# onspeed.net
KiCad netlist of a schematic drawn in EAGLE
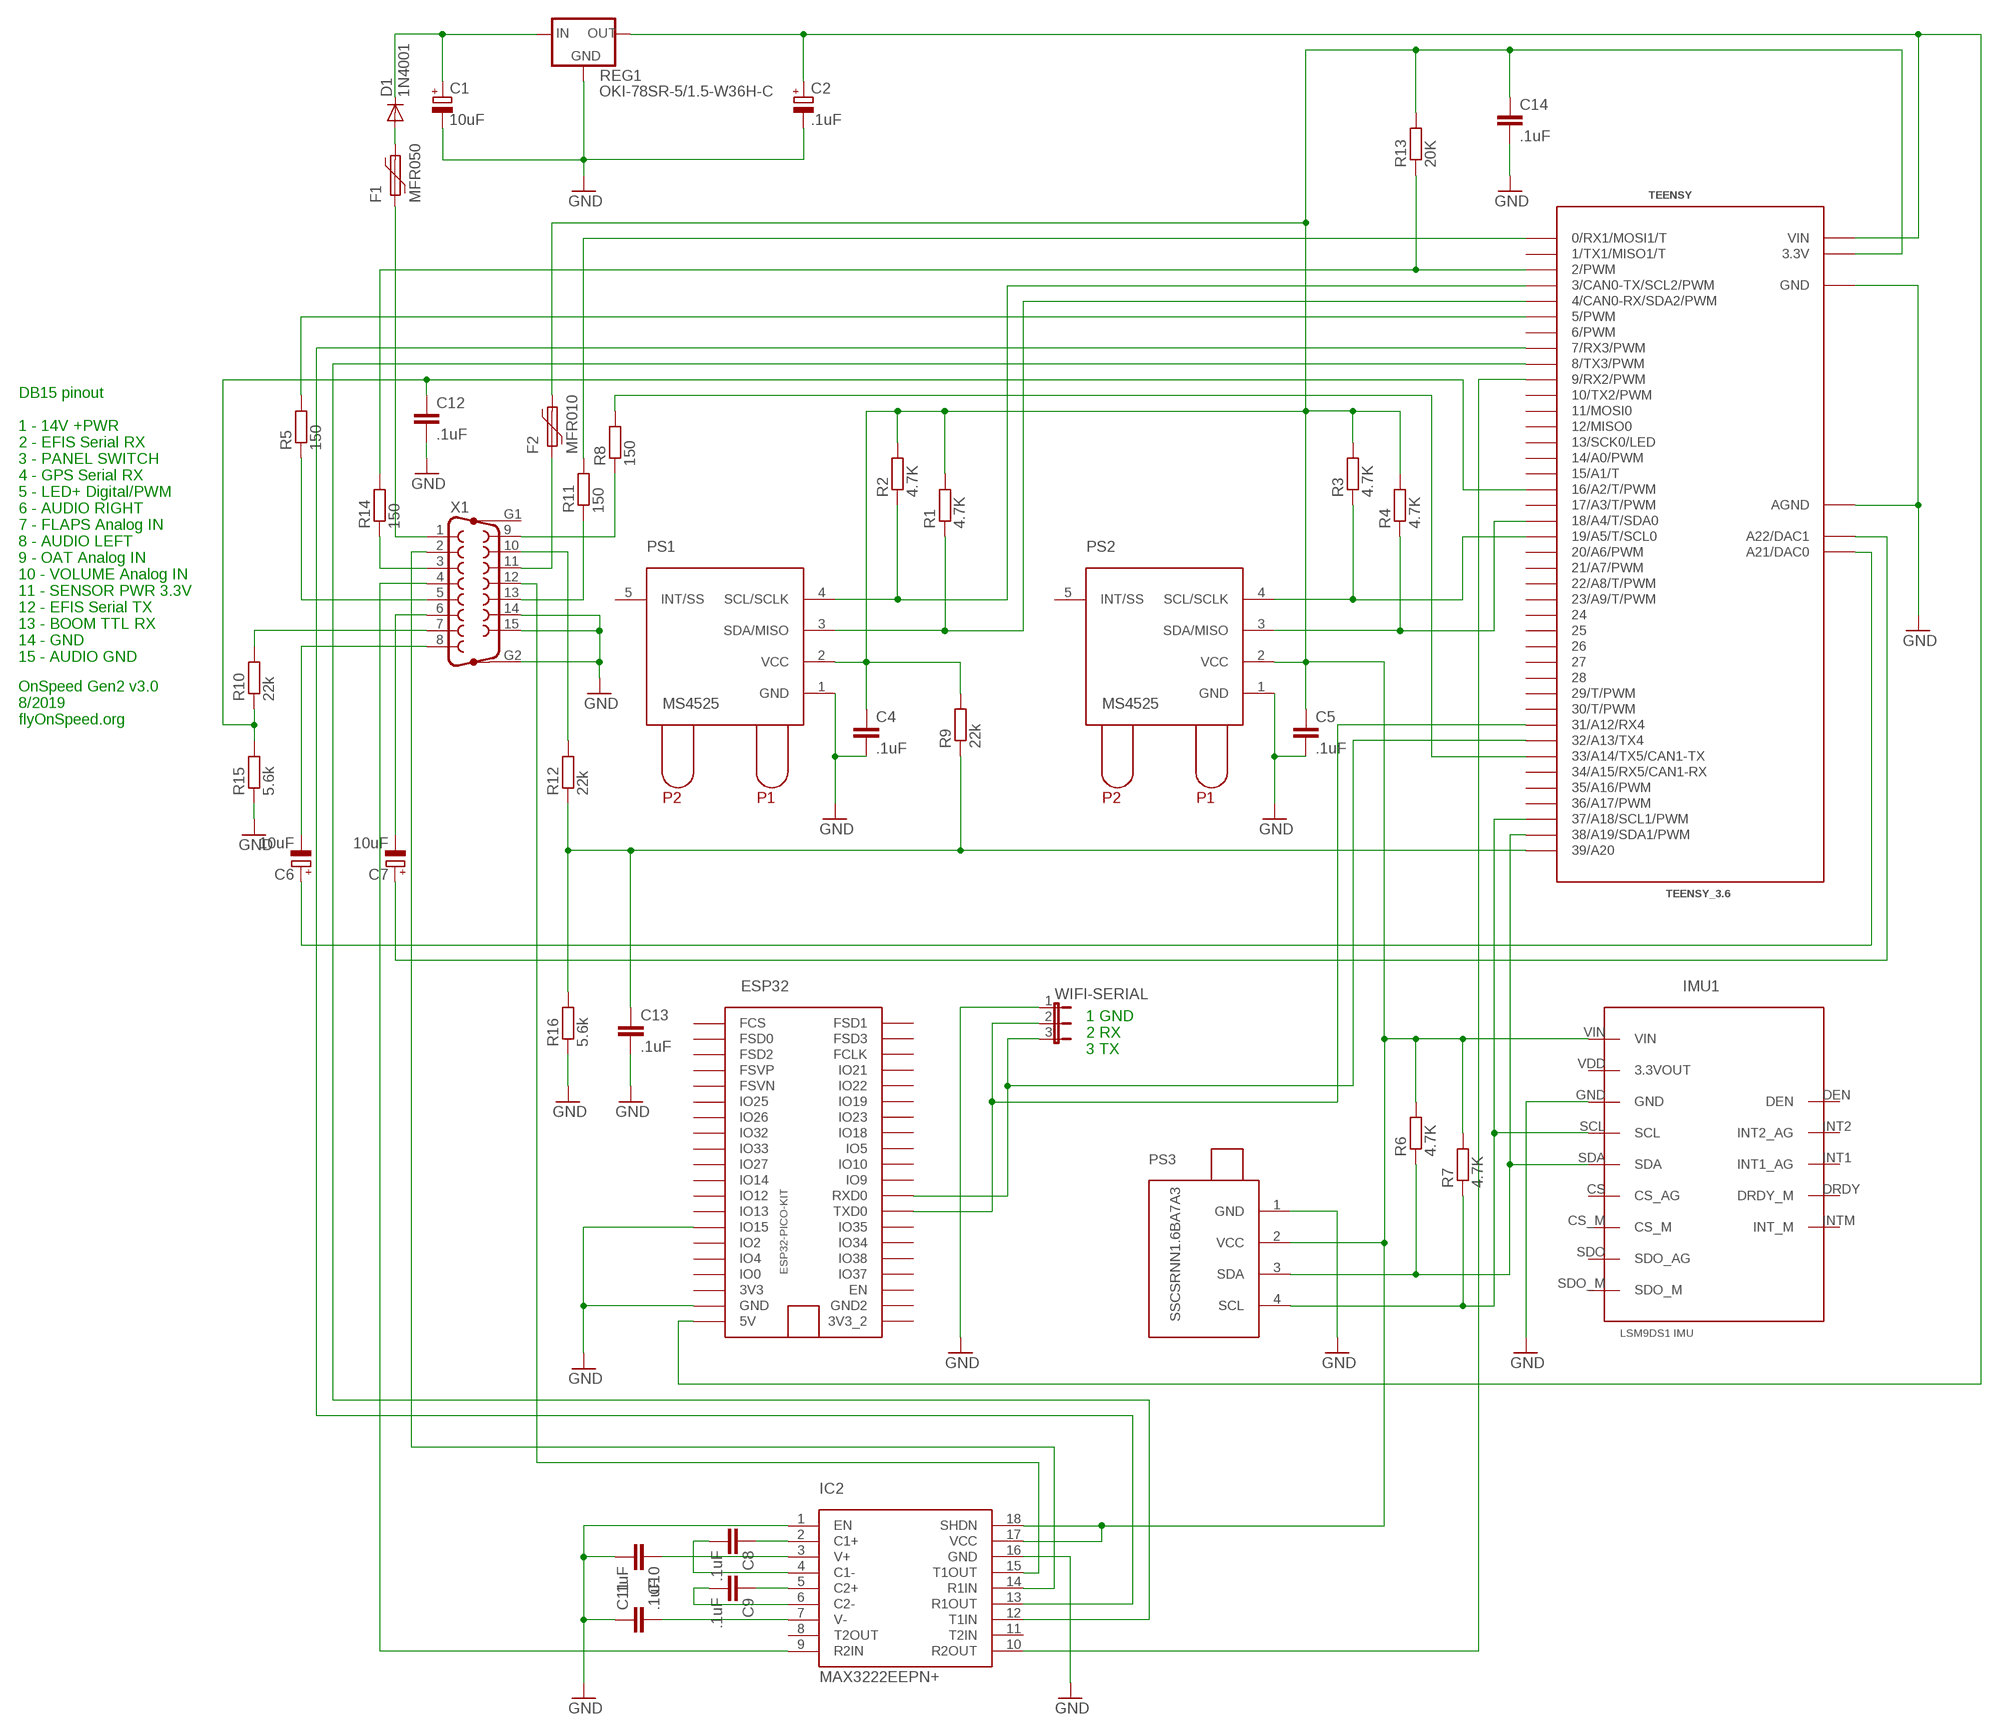
[diagram p0: schematic, sheet 1]

(export (version "E")
  (design (tool "Eeschema 10.0.6"))
  (components
    (comp (ref "C1")
      (value "10uF")
      (footprint "eagle-import:E2-5")
      (libsource (lib "eagle-import") (part "CPOL-EUE2-5"))
    )
    (comp (ref "C2")
      (value ".1uF")
      (footprint "eagle-import:E2-5")
      (libsource (lib "eagle-import") (part "CPOL-EUE2-5"))
    )
    (comp (ref "C4")
      (value ".1uF")
      (footprint "eagle-import:C025-025X050")
      (libsource (lib "eagle-import") (part "C-EU025-025X050"))
    )
    (comp (ref "C5")
      (value ".1uF")
      (footprint "eagle-import:C025-025X050")
      (libsource (lib "eagle-import") (part "C-EU025-025X050"))
    )
    (comp (ref "C6")
      (value "10uF")
      (footprint "eagle-import:E2-5")
      (libsource (lib "eagle-import") (part "CPOL-EUE2-5"))
    )
    (comp (ref "C7")
      (value "10uF")
      (footprint "eagle-import:E2-5")
      (libsource (lib "eagle-import") (part "CPOL-EUE2-5"))
    )
    (comp (ref "C8")
      (value ".1uF")
      (footprint "eagle-import:C025-025X050")
      (libsource (lib "eagle-import") (part "rcl_334_C-EU025-025X050"))
    )
    (comp (ref "C9")
      (value ".1uF")
      (footprint "eagle-import:C025-025X050")
      (libsource (lib "eagle-import") (part "rcl_334_C-EU025-025X050"))
    )
    (comp (ref "C10")
      (value ".1uF")
      (footprint "eagle-import:C025-025X050")
      (libsource (lib "eagle-import") (part "rcl_334_C-EU025-025X050"))
    )
    (comp (ref "C11")
      (value ".1uF")
      (footprint "eagle-import:C025-025X050")
      (libsource (lib "eagle-import") (part "rcl_334_C-EU025-025X050"))
    )
    (comp (ref "C12")
      (value ".1uF")
      (footprint "eagle-import:C025-025X050")
      (libsource (lib "eagle-import") (part "C-EU025-025X050"))
    )
    (comp (ref "C13")
      (value ".1uF")
      (footprint "eagle-import:C025-025X050")
      (libsource (lib "eagle-import") (part "C-EU025-025X050"))
    )
    (comp (ref "C14")
      (value ".1uF")
      (footprint "eagle-import:C025-025X050")
      (libsource (lib "eagle-import") (part "C-EU025-025X050"))
    )
    (comp (ref "D1")
      (value "1N4001")
      (footprint "eagle-import:DO41-10")
      (libsource (lib "eagle-import") (part "1N4001"))
    )
    (comp (ref "ESP32")
      (value "ESP32-PICO-KIT")
      (footprint "eagle-import:ESP32PICOKIT")
      (libsource (lib "eagle-import") (part "ESP32-PICO-KITPICO"))
    )
    (comp (ref "F1")
      (value "MFR050")
      (footprint "eagle-import:MF-5,1B")
      (libsource (lib "eagle-import") (part "MF-R055-5,1B"))
    )
    (comp (ref "F2")
      (value "MFR010")
      (footprint "eagle-import:MF-5,1B")
      (libsource (lib "eagle-import") (part "MF-R055-5,1B"))
    )
    (comp (ref "IC2")
      (value "MAX3222EEPN+")
      (footprint "eagle-import:DIL18")
      (libsource (lib "eagle-import") (part "MAX3222EEPN+"))
    )
    (comp (ref "IMU1")
      (value "LSM9DS1 IMU")
      (footprint "eagle-import:LSM9DS1_BREAKOUT")
      (libsource (lib "eagle-import") (part "LSM9DS1_BREAKOUT"))
    )
    (comp (ref "PS1")
      (value "MS4525")
      (footprint "eagle-import:DIL08-500")
      (libsource (lib "eagle-import") (part "MS4525"))
    )
    (comp (ref "PS2")
      (value "MS4525")
      (footprint "eagle-import:DIL08-500")
      (libsource (lib "eagle-import") (part "MS4525"))
    )
    (comp (ref "PS3")
      (value "SSCSRNN1.6BA7A3")
      (footprint "eagle-import:SIP-RN")
      (libsource (lib "eagle-import") (part "SSCSRNN1.6BA7A3"))
    )
    (comp (ref "R1")
      (value "4.7K")
      (footprint "eagle-import:0207_10")
      (libsource (lib "eagle-import") (part "R-EU_0207/10"))
    )
    (comp (ref "R2")
      (value "4.7K")
      (footprint "eagle-import:0207_10")
      (libsource (lib "eagle-import") (part "R-EU_0207/10"))
    )
    (comp (ref "R3")
      (value "4.7K")
      (footprint "eagle-import:0207_10")
      (libsource (lib "eagle-import") (part "R-EU_0207/10"))
    )
    (comp (ref "R4")
      (value "4.7K")
      (footprint "eagle-import:0207_10")
      (libsource (lib "eagle-import") (part "R-EU_0207/10"))
    )
    (comp (ref "R5")
      (value "150")
      (footprint "eagle-import:0207_10")
      (libsource (lib "eagle-import") (part "R-EU_0207/10"))
    )
    (comp (ref "R6")
      (value "4.7K")
      (footprint "eagle-import:0207_10")
      (libsource (lib "eagle-import") (part "R-EU_0207/10"))
    )
    (comp (ref "R7")
      (value "4.7K")
      (footprint "eagle-import:0207_10")
      (libsource (lib "eagle-import") (part "R-EU_0207/10"))
    )
    (comp (ref "R8")
      (value "150")
      (footprint "eagle-import:0207_10")
      (libsource (lib "eagle-import") (part "R-EU_0207/10"))
    )
    (comp (ref "R9")
      (value "22k")
      (footprint "eagle-import:0207_10")
      (libsource (lib "eagle-import") (part "R-EU_0207/10"))
    )
    (comp (ref "R10")
      (value "22k")
      (footprint "eagle-import:0207_10")
      (libsource (lib "eagle-import") (part "R-EU_0207/10"))
    )
    (comp (ref "R11")
      (value "150")
      (footprint "eagle-import:0207_10")
      (libsource (lib "eagle-import") (part "R-EU_0207/10"))
    )
    (comp (ref "R12")
      (value "22k")
      (footprint "eagle-import:0207_10")
      (libsource (lib "eagle-import") (part "R-EU_0207/10"))
    )
    (comp (ref "R13")
      (value "20K")
      (footprint "eagle-import:0207_10")
      (libsource (lib "eagle-import") (part "R-EU_0207/10"))
    )
    (comp (ref "R14")
      (value "150")
      (footprint "eagle-import:0207_10")
      (libsource (lib "eagle-import") (part "R-EU_0207/10"))
    )
    (comp (ref "R15")
      (value "5.6k")
      (footprint "eagle-import:0207_10")
      (libsource (lib "eagle-import") (part "R-EU_0207/10"))
    )
    (comp (ref "R16")
      (value "5.6k")
      (footprint "eagle-import:0207_10")
      (libsource (lib "eagle-import") (part "R-EU_0207/10"))
    )
    (comp (ref "REG1")
      (value "OKI-78SR-5/1.5-W36H-C")
      (footprint "eagle-import:SIP3H")
      (libsource (lib "eagle-import") (part "OKI-78SR-5/1.5-W36H-C"))
    )
    (comp (ref "TEENSY")
      (value "TEENSY_3.6")
      (footprint "eagle-import:TEENSY_3.6_DIL")
      (libsource (lib "eagle-import") (part "TEENSY_3.6_DIL"))
    )
    (comp (ref "WIFI-SERIAL")
      (value "JP2E")
      (footprint "eagle-import:JP2")
      (libsource (lib "eagle-import") (part "JP2E"))
    )
    (comp (ref "X1")
      (value "F15HP")
      (footprint "eagle-import:F15HP")
      (libsource (lib "eagle-import") (part "F15HP"))
    )
  )
  (nets
    (net (code "1") (name "GND") (class "Default")
      (node (ref "C1") (pin "-") (pinfunction "-_-") (pintype "passive"))
      (node (ref "C10") (pin "2") (pinfunction "2_2") (pintype "passive"))
      (node (ref "C11") (pin "1") (pinfunction "1_1") (pintype "passive"))
      (node (ref "C12") (pin "2") (pinfunction "2_2") (pintype "passive"))
      (node (ref "C13") (pin "2") (pinfunction "2_2") (pintype "passive"))
      (node (ref "C14") (pin "2") (pinfunction "2_2") (pintype "passive"))
      (node (ref "C2") (pin "-") (pinfunction "-_-") (pintype "passive"))
      (node (ref "C4") (pin "2") (pinfunction "2_2") (pintype "passive"))
      (node (ref "C5") (pin "2") (pinfunction "2_2") (pintype "passive"))
      (node (ref "ESP32") (pin "P$GND") (pinfunction "GND_P$GND") (pintype "bidirectional"))
      (node (ref "ESP32") (pin "P$IO15") (pinfunction "IO15_P$IO15") (pintype "bidirectional"))
      (node (ref "IC2") (pin "1") (pinfunction "EN_1") (pintype "bidirectional"))
      (node (ref "IC2") (pin "16") (pinfunction "GND_16") (pintype "bidirectional"))
      (node (ref "IMU1") (pin "GND") (pinfunction "GND_GND") (pintype "power_in"))
      (node (ref "PS1") (pin "1") (pinfunction "GND_1") (pintype "power_in"))
      (node (ref "PS2") (pin "1") (pinfunction "GND_1") (pintype "power_in"))
      (node (ref "PS3") (pin "1") (pinfunction "GND_1") (pintype "bidirectional"))
      (node (ref "R15") (pin "1") (pinfunction "1_1") (pintype "passive"))
      (node (ref "R16") (pin "1") (pinfunction "1_1") (pintype "passive"))
      (node (ref "REG1") (pin "2") (pinfunction "GND_2") (pintype "input"))
      (node (ref "TEENSY") (pin "AGND") (pinfunction "AGND_AGND") (pintype "power_in"))
      (node (ref "TEENSY") (pin "GND") (pinfunction "GND_GND") (pintype "power_in"))
      (node (ref "TEENSY") (pin "GND1") (pinfunction "GND_GND1") (pintype "power_in"))
      (node (ref "WIFI-SERIAL") (pin "1") (pinfunction "1_1") (pintype "passive"))
      (node (ref "X1") (pin "14") (pinfunction "14_14") (pintype "passive"))
      (node (ref "X1") (pin "15") (pinfunction "15_15") (pintype "passive"))
      (node (ref "X1") (pin "G2") (pinfunction "G2_G2") (pintype "passive"))
    )
    (net (code "2") (name "Net-(C6-Pad-)") (class "Default")
      (node (ref "C6") (pin "-") (pinfunction "-_-") (pintype "passive"))
      (node (ref "X1") (pin "8") (pinfunction "8_8") (pintype "passive"))
    )
    (net (code "3") (name "Net-(C7-Pad-)") (class "Default")
      (node (ref "C7") (pin "-") (pinfunction "-_-") (pintype "passive"))
      (node (ref "X1") (pin "6") (pinfunction "6_6") (pintype "passive"))
    )
    (net (code "4") (name "Net-(C13-Pad1)") (class "Default")
      (node (ref "C13") (pin "1") (pinfunction "1_1") (pintype "passive"))
      (node (ref "R12") (pin "1") (pinfunction "1_1") (pintype "passive"))
      (node (ref "R16") (pin "2") (pinfunction "2_2") (pintype "passive"))
      (node (ref "R9") (pin "1") (pinfunction "1_1") (pintype "passive"))
      (node (ref "TEENSY") (pin "39/A20") (pinfunction "39/A20_39/A20") (pintype "bidirectional"))
    )
    (net (code "5") (name "Net-(D1-PadA)") (class "Default")
      (node (ref "D1") (pin "A") (pinfunction "A_A") (pintype "passive"))
      (node (ref "F1") (pin "2") (pinfunction "2_2") (pintype "passive"))
    )
    (net (code "6") (name "Net-(ESP32-5V)") (class "Default")
      (node (ref "C2") (pin "+") (pinfunction "+_+") (pintype "passive"))
      (node (ref "ESP32") (pin "P$5V") (pinfunction "5V_P$5V") (pintype "bidirectional"))
      (node (ref "REG1") (pin "3") (pinfunction "OUT_3") (pintype "passive"))
      (node (ref "TEENSY") (pin "VIN") (pinfunction "VIN_VIN") (pintype "power_in"))
    )
    (net (code "7") (name "Net-(ESP32-RXD0)") (class "Default")
      (node (ref "ESP32") (pin "P$RXD0") (pinfunction "RXD0_P$RXD0") (pintype "bidirectional"))
      (node (ref "TEENSY") (pin "32/A13") (pinfunction "32/A13/TX4_32/A13") (pintype "bidirectional"))
      (node (ref "WIFI-SERIAL") (pin "3") (pinfunction "3_3") (pintype "passive"))
    )
    (net (code "8") (name "Net-(ESP32-TXD0)") (class "Default")
      (node (ref "ESP32") (pin "P$TXD0") (pinfunction "TXD0_P$TXD0") (pintype "bidirectional"))
      (node (ref "TEENSY") (pin "31/A12") (pinfunction "31/A12/RX4_31/A12") (pintype "bidirectional"))
      (node (ref "WIFI-SERIAL") (pin "2") (pinfunction "2_2") (pintype "passive"))
    )
    (net (code "9") (name "Net-(F1-Pad1)") (class "Default")
      (node (ref "F1") (pin "1") (pinfunction "1_1") (pintype "passive"))
      (node (ref "X1") (pin "1") (pinfunction "1_1") (pintype "passive"))
    )
    (net (code "10") (name "Net-(F2-Pad1)") (class "Default")
      (node (ref "F2") (pin "1") (pinfunction "1_1") (pintype "passive"))
      (node (ref "X1") (pin "11") (pinfunction "11_11") (pintype "passive"))
    )
    (net (code "11") (name "Net-(IC2-C1+)") (class "Default")
      (node (ref "C8") (pin "1") (pinfunction "1_1") (pintype "passive"))
      (node (ref "IC2") (pin "2") (pinfunction "C1+_2") (pintype "bidirectional"))
    )
    (net (code "12") (name "Net-(IC2-C1-)") (class "Default")
      (node (ref "C8") (pin "2") (pinfunction "2_2") (pintype "passive"))
      (node (ref "IC2") (pin "4") (pinfunction "C1-_4") (pintype "bidirectional"))
    )
    (net (code "13") (name "Net-(IC2-C2+)") (class "Default")
      (node (ref "C9") (pin "1") (pinfunction "1_1") (pintype "passive"))
      (node (ref "IC2") (pin "5") (pinfunction "C2+_5") (pintype "bidirectional"))
    )
    (net (code "14") (name "Net-(IC2-C2-)") (class "Default")
      (node (ref "C9") (pin "2") (pinfunction "2_2") (pintype "passive"))
      (node (ref "IC2") (pin "6") (pinfunction "C2-_6") (pintype "bidirectional"))
    )
    (net (code "15") (name "Net-(IC2-R1IN)") (class "Default")
      (node (ref "IC2") (pin "14") (pinfunction "R1IN_14") (pintype "bidirectional"))
      (node (ref "X1") (pin "2") (pinfunction "2_2") (pintype "passive"))
    )
    (net (code "16") (name "Net-(IC2-R1OUT)") (class "Default")
      (node (ref "IC2") (pin "13") (pinfunction "R1OUT_13") (pintype "bidirectional"))
      (node (ref "TEENSY") (pin "7") (pinfunction "7/RX3/PWM_7") (pintype "bidirectional"))
    )
    (net (code "17") (name "Net-(IC2-R2IN)") (class "Default")
      (node (ref "IC2") (pin "9") (pinfunction "R2IN_9") (pintype "bidirectional"))
      (node (ref "X1") (pin "4") (pinfunction "4_4") (pintype "passive"))
    )
    (net (code "18") (name "Net-(IC2-R2OUT)") (class "Default")
      (node (ref "IC2") (pin "10") (pinfunction "R2OUT_10") (pintype "bidirectional"))
      (node (ref "TEENSY") (pin "9") (pinfunction "9/RX2/PWM_9") (pintype "bidirectional"))
    )
    (net (code "19") (name "Net-(IC2-SHDN)") (class "Default")
      (node (ref "C14") (pin "1") (pinfunction "1_1") (pintype "passive"))
      (node (ref "C4") (pin "1") (pinfunction "1_1") (pintype "passive"))
      (node (ref "C5") (pin "1") (pinfunction "1_1") (pintype "passive"))
      (node (ref "F2") (pin "2") (pinfunction "2_2") (pintype "passive"))
      (node (ref "IC2") (pin "17") (pinfunction "VCC_17") (pintype "bidirectional"))
      (node (ref "IC2") (pin "18") (pinfunction "SHDN_18") (pintype "bidirectional"))
      (node (ref "IMU1") (pin "VIN") (pinfunction "VIN_VIN") (pintype "power_in"))
      (node (ref "PS1") (pin "2") (pinfunction "VCC_2") (pintype "power_in"))
      (node (ref "PS2") (pin "2") (pinfunction "VCC_2") (pintype "power_in"))
      (node (ref "PS3") (pin "2") (pinfunction "VCC_2") (pintype "bidirectional"))
      (node (ref "R1") (pin "2") (pinfunction "2_2") (pintype "passive"))
      (node (ref "R13") (pin "2") (pinfunction "2_2") (pintype "passive"))
      (node (ref "R2") (pin "2") (pinfunction "2_2") (pintype "passive"))
      (node (ref "R3") (pin "2") (pinfunction "2_2") (pintype "passive"))
      (node (ref "R4") (pin "2") (pinfunction "2_2") (pintype "passive"))
      (node (ref "R6") (pin "2") (pinfunction "2_2") (pintype "passive"))
      (node (ref "R7") (pin "2") (pinfunction "2_2") (pintype "passive"))
      (node (ref "R9") (pin "2") (pinfunction "2_2") (pintype "passive"))
      (node (ref "TEENSY") (pin "3.3V") (pinfunction "3.3V_3.3V") (pintype "power_in"))
      (node (ref "TEENSY") (pin "3.3V3") (pinfunction "3.3V_3.3V3") (pintype "power_in"))
    )
    (net (code "20") (name "Net-(IC2-T1IN)") (class "Default")
      (node (ref "IC2") (pin "12") (pinfunction "T1IN_12") (pintype "bidirectional"))
      (node (ref "TEENSY") (pin "8") (pinfunction "8/TX3/PWM_8") (pintype "bidirectional"))
    )
    (net (code "21") (name "Net-(IC2-T1OUT)") (class "Default")
      (node (ref "IC2") (pin "15") (pinfunction "T1OUT_15") (pintype "bidirectional"))
      (node (ref "X1") (pin "12") (pinfunction "12_12") (pintype "passive"))
    )
    (net (code "22") (name "Net-(IC2-V+)") (class "Default")
      (node (ref "C10") (pin "1") (pinfunction "1_1") (pintype "passive"))
      (node (ref "IC2") (pin "3") (pinfunction "V+_3") (pintype "bidirectional"))
    )
    (net (code "23") (name "Net-(IC2-V-)") (class "Default")
      (node (ref "C11") (pin "2") (pinfunction "2_2") (pintype "passive"))
      (node (ref "IC2") (pin "7") (pinfunction "V-_7") (pintype "bidirectional"))
    )
    (net (code "24") (name "Net-(PS1-SCL{slash}SCLK)") (class "Default")
      (node (ref "PS1") (pin "4") (pinfunction "SCL/SCLK_4") (pintype "bidirectional"))
      (node (ref "R2") (pin "1") (pinfunction "1_1") (pintype "passive"))
      (node (ref "TEENSY") (pin "3") (pinfunction "3/CAN0-TX/SCL2/PWM_3") (pintype "bidirectional"))
    )
    (net (code "25") (name "Net-(PS1-SDA{slash}MISO)") (class "Default")
      (node (ref "PS1") (pin "3") (pinfunction "SDA/MISO_3") (pintype "bidirectional"))
      (node (ref "R1") (pin "1") (pinfunction "1_1") (pintype "passive"))
      (node (ref "TEENSY") (pin "4") (pinfunction "4/CAN0-RX/SDA2/PWM_4") (pintype "bidirectional"))
    )
    (net (code "26") (name "Net-(PS2-SCL{slash}SCLK)") (class "Default")
      (node (ref "PS2") (pin "4") (pinfunction "SCL/SCLK_4") (pintype "bidirectional"))
      (node (ref "R3") (pin "1") (pinfunction "1_1") (pintype "passive"))
      (node (ref "TEENSY") (pin "19/A5") (pinfunction "19/A5/T/SCL0_19/A5") (pintype "bidirectional"))
    )
    (net (code "27") (name "Net-(PS2-SDA{slash}MISO)") (class "Default")
      (node (ref "PS2") (pin "3") (pinfunction "SDA/MISO_3") (pintype "bidirectional"))
      (node (ref "R4") (pin "1") (pinfunction "1_1") (pintype "passive"))
      (node (ref "TEENSY") (pin "18/A4") (pinfunction "18/A4/T/SDA0_18/A4") (pintype "bidirectional"))
    )
    (net (code "28") (name "Net-(PS3-SCL)") (class "Default")
      (node (ref "IMU1") (pin "SCL") (pinfunction "SCL_SCL") (pintype "bidirectional"))
      (node (ref "PS3") (pin "4") (pinfunction "SCL_4") (pintype "bidirectional"))
      (node (ref "R7") (pin "1") (pinfunction "1_1") (pintype "passive"))
      (node (ref "TEENSY") (pin "37/A18") (pinfunction "37/A18/SCL1/PWM_37/A18") (pintype "bidirectional"))
    )
    (net (code "29") (name "Net-(PS3-SDA)") (class "Default")
      (node (ref "IMU1") (pin "SDA") (pinfunction "SDA_SDA") (pintype "bidirectional"))
      (node (ref "PS3") (pin "3") (pinfunction "SDA_3") (pintype "bidirectional"))
      (node (ref "R6") (pin "1") (pinfunction "1_1") (pintype "passive"))
      (node (ref "TEENSY") (pin "38/A19") (pinfunction "38/A19/SDA1/PWM_38/A19") (pintype "bidirectional"))
    )
    (net (code "30") (name "Net-(R5-Pad1)") (class "Default")
      (node (ref "R5") (pin "1") (pinfunction "1_1") (pintype "passive"))
      (node (ref "X1") (pin "5") (pinfunction "5_5") (pintype "passive"))
    )
    (net (code "31") (name "Net-(R8-Pad1)") (class "Default")
      (node (ref "R8") (pin "1") (pinfunction "1_1") (pintype "passive"))
      (node (ref "X1") (pin "9") (pinfunction "9_9") (pintype "passive"))
    )
    (net (code "32") (name "Net-(R10-Pad2)") (class "Default")
      (node (ref "R10") (pin "2") (pinfunction "2_2") (pintype "passive"))
      (node (ref "X1") (pin "7") (pinfunction "7_7") (pintype "passive"))
    )
    (net (code "33") (name "Net-(R11-Pad1)") (class "Default")
      (node (ref "R11") (pin "1") (pinfunction "1_1") (pintype "passive"))
      (node (ref "X1") (pin "13") (pinfunction "13_13") (pintype "passive"))
    )
    (net (code "34") (name "Net-(R12-Pad2)") (class "Default")
      (node (ref "R12") (pin "2") (pinfunction "2_2") (pintype "passive"))
      (node (ref "X1") (pin "10") (pinfunction "10_10") (pintype "passive"))
    )
    (net (code "35") (name "Net-(R14-Pad1)") (class "Default")
      (node (ref "R14") (pin "1") (pinfunction "1_1") (pintype "passive"))
      (node (ref "X1") (pin "3") (pinfunction "3_3") (pintype "passive"))
    )
    (net (code "36") (name "Net-(REG1-IN)") (class "Default")
      (node (ref "C1") (pin "+") (pinfunction "+_+") (pintype "passive"))
      (node (ref "D1") (pin "C") (pinfunction "C_C") (pintype "passive"))
      (node (ref "REG1") (pin "1") (pinfunction "IN_1") (pintype "input"))
    )
    (net (code "37") (name "Net-(TEENSY-0{slash}RX1{slash}MOSI1{slash}T)") (class "Default")
      (node (ref "R11") (pin "2") (pinfunction "2_2") (pintype "passive"))
      (node (ref "TEENSY") (pin "0") (pinfunction "0/RX1/MOSI1/T_0") (pintype "bidirectional"))
    )
    (net (code "38") (name "Net-(TEENSY-2{slash}PWM)") (class "Default")
      (node (ref "R13") (pin "1") (pinfunction "1_1") (pintype "passive"))
      (node (ref "R14") (pin "2") (pinfunction "2_2") (pintype "passive"))
      (node (ref "TEENSY") (pin "2") (pinfunction "2/PWM_2") (pintype "bidirectional"))
    )
    (net (code "39") (name "Net-(TEENSY-5{slash}PWM)") (class "Default")
      (node (ref "R5") (pin "2") (pinfunction "2_2") (pintype "passive"))
      (node (ref "TEENSY") (pin "5") (pinfunction "5/PWM_5") (pintype "bidirectional"))
    )
    (net (code "40") (name "Net-(TEENSY-16{slash}A2{slash}T{slash}PWM)") (class "Default")
      (node (ref "C12") (pin "1") (pinfunction "1_1") (pintype "passive"))
      (node (ref "R10") (pin "1") (pinfunction "1_1") (pintype "passive"))
      (node (ref "R15") (pin "2") (pinfunction "2_2") (pintype "passive"))
      (node (ref "TEENSY") (pin "16/A2") (pinfunction "16/A2/T/PWM_16/A2") (pintype "bidirectional"))
    )
    (net (code "41") (name "Net-(TEENSY-33{slash}A14{slash}TX5{slash}CAN1-TX)") (class "Default")
      (node (ref "R8") (pin "2") (pinfunction "2_2") (pintype "passive"))
      (node (ref "TEENSY") (pin "33/A14") (pinfunction "33/A14/TX5/CAN1-TX_33/A14") (pintype "bidirectional"))
    )
    (net (code "42") (name "Net-(TEENSY-A21{slash}DAC0)") (class "Default")
      (node (ref "C6") (pin "+") (pinfunction "+_+") (pintype "passive"))
      (node (ref "TEENSY") (pin "A21") (pinfunction "A21/DAC0_A21") (pintype "bidirectional"))
    )
    (net (code "43") (name "Net-(TEENSY-A22{slash}DAC1)") (class "Default")
      (node (ref "C7") (pin "+") (pinfunction "+_+") (pintype "passive"))
      (node (ref "TEENSY") (pin "A22") (pinfunction "A22/DAC1_A22") (pintype "bidirectional"))
    )
    (net (code "44") (name "unconnected-(ESP32-3V3-PadP$3V3)") (class "Default")
      (node (ref "ESP32") (pin "P$3V3") (pinfunction "3V3_P$3V3") (pintype "bidirectional"))
    )
    (net (code "45") (name "unconnected-(ESP32-3V3_2-PadP$3V3_2)") (class "Default")
      (node (ref "ESP32") (pin "P$3V3_2") (pinfunction "3V3_2_P$3V3_2") (pintype "bidirectional"))
    )
    (net (code "46") (name "unconnected-(ESP32-EN-PadP$EN)") (class "Default")
      (node (ref "ESP32") (pin "P$EN") (pinfunction "EN_P$EN") (pintype "bidirectional"))
    )
    (net (code "47") (name "unconnected-(ESP32-FCLK-PadP$FCLK)") (class "Default")
      (node (ref "ESP32") (pin "P$FCLK") (pinfunction "FCLK_P$FCLK") (pintype "bidirectional"))
    )
    (net (code "48") (name "unconnected-(ESP32-FCS-PadP$FCS)") (class "Default")
      (node (ref "ESP32") (pin "P$FCS") (pinfunction "FCS_P$FCS") (pintype "bidirectional"))
    )
    (net (code "49") (name "unconnected-(ESP32-FSD0-PadP$FSD0)") (class "Default")
      (node (ref "ESP32") (pin "P$FSD0") (pinfunction "FSD0_P$FSD0") (pintype "bidirectional"))
    )
    (net (code "50") (name "unconnected-(ESP32-FSD1-PadP$FSD1)") (class "Default")
      (node (ref "ESP32") (pin "P$FSD1") (pinfunction "FSD1_P$FSD1") (pintype "bidirectional"))
    )
    (net (code "51") (name "unconnected-(ESP32-FSD2-PadP$FSD2)") (class "Default")
      (node (ref "ESP32") (pin "P$FSD2") (pinfunction "FSD2_P$FSD2") (pintype "bidirectional"))
    )
    (net (code "52") (name "unconnected-(ESP32-FSD3-PadP$FSD3)") (class "Default")
      (node (ref "ESP32") (pin "P$FSD3") (pinfunction "FSD3_P$FSD3") (pintype "bidirectional"))
    )
    (net (code "53") (name "unconnected-(ESP32-FSVN-PadP$FSVN)") (class "Default")
      (node (ref "ESP32") (pin "P$FSVN") (pinfunction "FSVN_P$FSVN") (pintype "bidirectional"))
    )
    (net (code "54") (name "unconnected-(ESP32-FSVP-PadP$FSVP)") (class "Default")
      (node (ref "ESP32") (pin "P$FSVP") (pinfunction "FSVP_P$FSVP") (pintype "bidirectional"))
    )
    (net (code "55") (name "unconnected-(ESP32-GND2-PadP$GND2)") (class "Default")
      (node (ref "ESP32") (pin "P$GND2") (pinfunction "GND2_P$GND2") (pintype "bidirectional"))
    )
    (net (code "56") (name "unconnected-(ESP32-IO0-PadP$IO0)") (class "Default")
      (node (ref "ESP32") (pin "P$IO0") (pinfunction "IO0_P$IO0") (pintype "bidirectional"))
    )
    (net (code "57") (name "unconnected-(ESP32-IO2-PadP$IO2)") (class "Default")
      (node (ref "ESP32") (pin "P$IO2") (pinfunction "IO2_P$IO2") (pintype "bidirectional"))
    )
    (net (code "58") (name "unconnected-(ESP32-IO4-PadP$IO4)") (class "Default")
      (node (ref "ESP32") (pin "P$IO4") (pinfunction "IO4_P$IO4") (pintype "bidirectional"))
    )
    (net (code "59") (name "unconnected-(ESP32-IO5-PadP$IO5)") (class "Default")
      (node (ref "ESP32") (pin "P$IO5") (pinfunction "IO5_P$IO5") (pintype "bidirectional"))
    )
    (net (code "60") (name "unconnected-(ESP32-IO9-PadP$IO9)") (class "Default")
      (node (ref "ESP32") (pin "P$IO9") (pinfunction "IO9_P$IO9") (pintype "bidirectional"))
    )
    (net (code "61") (name "unconnected-(ESP32-IO10-PadP$IO10)") (class "Default")
      (node (ref "ESP32") (pin "P$IO10") (pinfunction "IO10_P$IO10") (pintype "bidirectional"))
    )
    (net (code "62") (name "unconnected-(ESP32-IO12-PadP$IO12)") (class "Default")
      (node (ref "ESP32") (pin "P$IO12") (pinfunction "IO12_P$IO12") (pintype "bidirectional"))
    )
    (net (code "63") (name "unconnected-(ESP32-IO13-PadP$IO13)") (class "Default")
      (node (ref "ESP32") (pin "P$IO13") (pinfunction "IO13_P$IO13") (pintype "bidirectional"))
    )
    (net (code "64") (name "unconnected-(ESP32-IO14-PadP$IO14)") (class "Default")
      (node (ref "ESP32") (pin "P$IO14") (pinfunction "IO14_P$IO14") (pintype "bidirectional"))
    )
    (net (code "65") (name "unconnected-(ESP32-IO18-PadP$IO18)") (class "Default")
      (node (ref "ESP32") (pin "P$IO18") (pinfunction "IO18_P$IO18") (pintype "bidirectional"))
    )
    (net (code "66") (name "unconnected-(ESP32-IO19-PadP$IO19)") (class "Default")
      (node (ref "ESP32") (pin "P$IO19") (pinfunction "IO19_P$IO19") (pintype "bidirectional"))
    )
    (net (code "67") (name "unconnected-(ESP32-IO21-PadP$IO21)") (class "Default")
      (node (ref "ESP32") (pin "P$IO21") (pinfunction "IO21_P$IO21") (pintype "bidirectional"))
    )
    (net (code "68") (name "unconnected-(ESP32-IO22-PadP$IO22)") (class "Default")
      (node (ref "ESP32") (pin "P$IO22") (pinfunction "IO22_P$IO22") (pintype "bidirectional"))
    )
    (net (code "69") (name "unconnected-(ESP32-IO23-PadP$IO23)") (class "Default")
      (node (ref "ESP32") (pin "P$IO23") (pinfunction "IO23_P$IO23") (pintype "bidirectional"))
    )
    (net (code "70") (name "unconnected-(ESP32-IO25-PadP$IO25)") (class "Default")
      (node (ref "ESP32") (pin "P$IO25") (pinfunction "IO25_P$IO25") (pintype "bidirectional"))
    )
    (net (code "71") (name "unconnected-(ESP32-IO26-PadP$IO26)") (class "Default")
      (node (ref "ESP32") (pin "P$IO26") (pinfunction "IO26_P$IO26") (pintype "bidirectional"))
    )
    (net (code "72") (name "unconnected-(ESP32-IO27-PadP$IO27)") (class "Default")
      (node (ref "ESP32") (pin "P$IO27") (pinfunction "IO27_P$IO27") (pintype "bidirectional"))
    )
    (net (code "73") (name "unconnected-(ESP32-IO32-PadP$IO32)") (class "Default")
      (node (ref "ESP32") (pin "P$IO32") (pinfunction "IO32_P$IO32") (pintype "bidirectional"))
    )
    (net (code "74") (name "unconnected-(ESP32-IO33-PadP$IO33)") (class "Default")
      (node (ref "ESP32") (pin "P$IO33") (pinfunction "IO33_P$IO33") (pintype "bidirectional"))
    )
    (net (code "75") (name "unconnected-(ESP32-IO34-PadP$IO34)") (class "Default")
      (node (ref "ESP32") (pin "P$IO34") (pinfunction "IO34_P$IO34") (pintype "bidirectional"))
    )
    (net (code "76") (name "unconnected-(ESP32-IO35-PadP$IO35)") (class "Default")
      (node (ref "ESP32") (pin "P$IO35") (pinfunction "IO35_P$IO35") (pintype "bidirectional"))
    )
    (net (code "77") (name "unconnected-(ESP32-IO37-PadP$IO37)") (class "Default")
      (node (ref "ESP32") (pin "P$IO37") (pinfunction "IO37_P$IO37") (pintype "bidirectional"))
    )
    (net (code "78") (name "unconnected-(ESP32-IO38-PadP$IO38)") (class "Default")
      (node (ref "ESP32") (pin "P$IO38") (pinfunction "IO38_P$IO38") (pintype "bidirectional"))
    )
    (net (code "79") (name "unconnected-(IC2-T2IN-Pad11)") (class "Default")
      (node (ref "IC2") (pin "11") (pinfunction "T2IN_11") (pintype "bidirectional"))
    )
    (net (code "80") (name "unconnected-(IC2-T2OUT-Pad8)") (class "Default")
      (node (ref "IC2") (pin "8") (pinfunction "T2OUT_8") (pintype "bidirectional"))
    )
    (net (code "81") (name "unconnected-(IMU1-3.3VOUT-PadVDD)") (class "Default")
      (node (ref "IMU1") (pin "VDD") (pinfunction "3.3VOUT_VDD") (pintype "output"))
    )
    (net (code "82") (name "unconnected-(IMU1-CS_AG-PadCS)") (class "Default")
      (node (ref "IMU1") (pin "CS") (pinfunction "CS_AG_CS") (pintype "bidirectional"))
    )
    (net (code "83") (name "unconnected-(IMU1-DRDY_M-PadDRDY)") (class "Default")
      (node (ref "IMU1") (pin "DRDY") (pinfunction "DRDY_M_DRDY") (pintype "bidirectional"))
    )
    (net (code "84") (name "unconnected-(IMU1-INT1_AG-PadINT1)") (class "Default")
      (node (ref "IMU1") (pin "INT1") (pinfunction "INT1_AG_INT1") (pintype "bidirectional"))
    )
    (net (code "85") (name "unconnected-(IMU1-INT2_AG-PadINT2)") (class "Default")
      (node (ref "IMU1") (pin "INT2") (pinfunction "INT2_AG_INT2") (pintype "bidirectional"))
    )
    (net (code "86") (name "unconnected-(IMU1-INT_M-PadINTM)") (class "Default")
      (node (ref "IMU1") (pin "INTM") (pinfunction "INT_M_INTM") (pintype "bidirectional"))
    )
    (net (code "87") (name "unconnected-(IMU1-PadCS_M)") (class "Default")
      (node (ref "IMU1") (pin "CS_M") (pinfunction "CS_M_CS_M") (pintype "bidirectional"))
    )
    (net (code "88") (name "unconnected-(IMU1-PadDEN)") (class "Default")
      (node (ref "IMU1") (pin "DEN") (pinfunction "DEN_DEN") (pintype "bidirectional"))
    )
    (net (code "89") (name "unconnected-(IMU1-PadSDO_M)") (class "Default")
      (node (ref "IMU1") (pin "SDO_M") (pinfunction "SDO_M_SDO_M") (pintype "bidirectional"))
    )
    (net (code "90") (name "unconnected-(IMU1-SDO_AG-PadSDO)") (class "Default")
      (node (ref "IMU1") (pin "SDO") (pinfunction "SDO_AG_SDO") (pintype "bidirectional"))
    )
    (net (code "91") (name "unconnected-(PS1-INT{slash}SS-Pad5)") (class "Default")
      (node (ref "PS1") (pin "5") (pinfunction "INT/SS_5") (pintype "bidirectional"))
    )
    (net (code "92") (name "unconnected-(PS2-INT{slash}SS-Pad5)") (class "Default")
      (node (ref "PS2") (pin "5") (pinfunction "INT/SS_5") (pintype "bidirectional"))
    )
    (net (code "93") (name "unconnected-(TEENSY-1{slash}TX1{slash}MISO1{slash}T-Pad1)") (class "Default")
      (node (ref "TEENSY") (pin "1") (pinfunction "1/TX1/MISO1/T_1") (pintype "bidirectional"))
    )
    (net (code "94") (name "unconnected-(TEENSY-6{slash}PWM-Pad6)") (class "Default")
      (node (ref "TEENSY") (pin "6") (pinfunction "6/PWM_6") (pintype "bidirectional"))
    )
    (net (code "95") (name "unconnected-(TEENSY-10{slash}TX2{slash}PWM-Pad10)") (class "Default")
      (node (ref "TEENSY") (pin "10") (pinfunction "10/TX2/PWM_10") (pintype "bidirectional"))
    )
    (net (code "96") (name "unconnected-(TEENSY-11{slash}MOSI0-Pad11)") (class "Default")
      (node (ref "TEENSY") (pin "11") (pinfunction "11/MOSI0_11") (pintype "bidirectional"))
    )
    (net (code "97") (name "unconnected-(TEENSY-12{slash}MISO0-Pad12)") (class "Default")
      (node (ref "TEENSY") (pin "12") (pinfunction "12/MISO0_12") (pintype "bidirectional"))
    )
    (net (code "98") (name "unconnected-(TEENSY-13{slash}SCK0{slash}LED-Pad13)") (class "Default")
      (node (ref "TEENSY") (pin "13") (pinfunction "13/SCK0/LED_13") (pintype "bidirectional"))
    )
    (net (code "99") (name "unconnected-(TEENSY-14{slash}A0{slash}PWM-Pad14{slash}A0)") (class "Default")
      (node (ref "TEENSY") (pin "14/A0") (pinfunction "14/A0/PWM_14/A0") (pintype "bidirectional"))
    )
    (net (code "100") (name "unconnected-(TEENSY-15{slash}A1{slash}T-Pad15{slash}A1)") (class "Default")
      (node (ref "TEENSY") (pin "15/A1") (pinfunction "15/A1/T_15/A1") (pintype "bidirectional"))
    )
    (net (code "101") (name "unconnected-(TEENSY-17{slash}A3{slash}T{slash}PWM-Pad17{slash}A3)") (class "Default")
      (node (ref "TEENSY") (pin "17/A3") (pinfunction "17/A3/T/PWM_17/A3") (pintype "bidirectional"))
    )
    (net (code "102") (name "unconnected-(TEENSY-20{slash}A6{slash}PWM-Pad20{slash}A6)") (class "Default")
      (node (ref "TEENSY") (pin "20/A6") (pinfunction "20/A6/PWM_20/A6") (pintype "bidirectional"))
    )
    (net (code "103") (name "unconnected-(TEENSY-21{slash}A7{slash}PWM-Pad21{slash}A7)") (class "Default")
      (node (ref "TEENSY") (pin "21/A7") (pinfunction "21/A7/PWM_21/A7") (pintype "bidirectional"))
    )
    (net (code "104") (name "unconnected-(TEENSY-22{slash}A8{slash}T{slash}PWM-Pad22{slash}A8)") (class "Default")
      (node (ref "TEENSY") (pin "22/A8") (pinfunction "22/A8/T/PWM_22/A8") (pintype "bidirectional"))
    )
    (net (code "105") (name "unconnected-(TEENSY-23{slash}A9{slash}T{slash}PWM-Pad23{slash}A9)") (class "Default")
      (node (ref "TEENSY") (pin "23/A9") (pinfunction "23/A9/T/PWM_23/A9") (pintype "bidirectional"))
    )
    (net (code "106") (name "unconnected-(TEENSY-29{slash}T{slash}PWM-Pad29)") (class "Default")
      (node (ref "TEENSY") (pin "29") (pinfunction "29/T/PWM_29") (pintype "bidirectional"))
    )
    (net (code "107") (name "unconnected-(TEENSY-30{slash}T{slash}PWM-Pad30)") (class "Default")
      (node (ref "TEENSY") (pin "30") (pinfunction "30/T/PWM_30") (pintype "bidirectional"))
    )
    (net (code "108") (name "unconnected-(TEENSY-34{slash}A15{slash}RX5{slash}CAN1-RX-Pad34{slash}A15)") (class "Default")
      (node (ref "TEENSY") (pin "34/A15") (pinfunction "34/A15/RX5/CAN1-RX_34/A15") (pintype "bidirectional"))
    )
    (net (code "109") (name "unconnected-(TEENSY-35{slash}A16{slash}PWM-Pad35{slash}A16)") (class "Default")
      (node (ref "TEENSY") (pin "35/A16") (pinfunction "35/A16/PWM_35/A16") (pintype "bidirectional"))
    )
    (net (code "110") (name "unconnected-(TEENSY-36{slash}A17{slash}PWM-Pad36{slash}A17)") (class "Default")
      (node (ref "TEENSY") (pin "36/A17") (pinfunction "36/A17/PWM_36/A17") (pintype "bidirectional"))
    )
    (net (code "111") (name "unconnected-(TEENSY-Pad24)") (class "Default")
      (node (ref "TEENSY") (pin "24") (pinfunction "24_24") (pintype "bidirectional"))
    )
    (net (code "112") (name "unconnected-(TEENSY-Pad25)") (class "Default")
      (node (ref "TEENSY") (pin "25") (pinfunction "25_25") (pintype "bidirectional"))
    )
    (net (code "113") (name "unconnected-(TEENSY-Pad26)") (class "Default")
      (node (ref "TEENSY") (pin "26") (pinfunction "26_26") (pintype "bidirectional"))
    )
    (net (code "114") (name "unconnected-(TEENSY-Pad27)") (class "Default")
      (node (ref "TEENSY") (pin "27") (pinfunction "27_27") (pintype "bidirectional"))
    )
    (net (code "115") (name "unconnected-(TEENSY-Pad28)") (class "Default")
      (node (ref "TEENSY") (pin "28") (pinfunction "28_28") (pintype "bidirectional"))
    )
    (net (code "116") (name "unconnected-(X1-PadG1)") (class "Default")
      (node (ref "X1") (pin "G1") (pinfunction "G1_G1") (pintype "passive"))
    )
  )
)
